# ba662.net
KiCad netlist of a schematic drawn in EAGLE
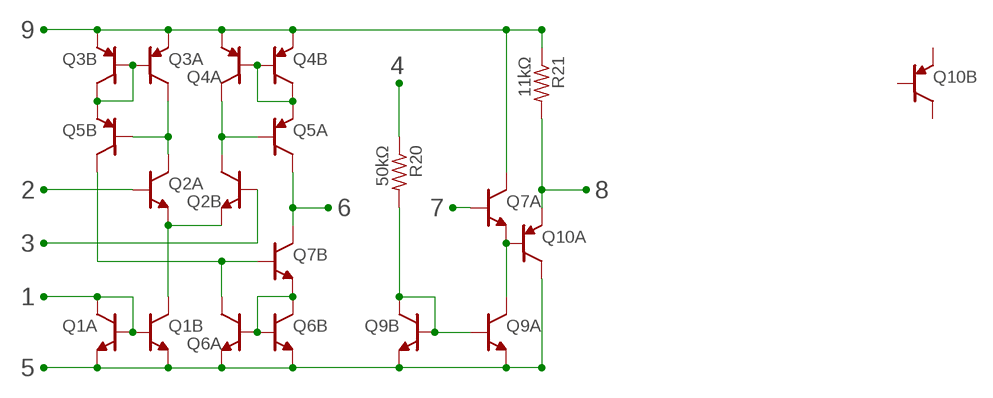
[diagram p0: schematic, sheet 1]

(export (version "E")
  (design (tool "Eeschema 10.0.6"))
  (components
    (comp (ref "Q1")
      (value "NPN-DUALPMP4201")
      (footprint "eagle-import:SOT363")
      (libsource (lib "eagle-import") (part "NPN-DUALPMP4201"))
    )
    (comp (ref "Q2")
      (value "NPN-DUALPMP4201")
      (footprint "eagle-import:SOT363")
      (libsource (lib "eagle-import") (part "NPN-DUALPMP4201"))
    )
    (comp (ref "Q3")
      (value "PNP-DUALPMP5201")
      (footprint "eagle-import:SOT363")
      (libsource (lib "eagle-import") (part "PNP-DUALPMP5201"))
    )
    (comp (ref "Q4")
      (value "PNP-DUALPMP5201")
      (footprint "eagle-import:SOT363")
      (libsource (lib "eagle-import") (part "PNP-DUALPMP5201"))
    )
    (comp (ref "Q5")
      (value "PNP-DUALPMP5201")
      (footprint "eagle-import:SOT363")
      (libsource (lib "eagle-import") (part "PNP-DUALPMP5201"))
    )
    (comp (ref "Q6")
      (value "NPN-DUALPMP4201")
      (footprint "eagle-import:SOT363")
      (libsource (lib "eagle-import") (part "NPN-DUALPMP4201"))
    )
    (comp (ref "Q7")
      (value "NPN-DUALPMP4201")
      (footprint "eagle-import:SOT363")
      (libsource (lib "eagle-import") (part "NPN-DUALPMP4201"))
    )
    (comp (ref "Q9")
      (value "NPN-DUALPMP4201")
      (footprint "eagle-import:SOT363")
      (libsource (lib "eagle-import") (part "NPN-DUALPMP4201"))
    )
    (comp (ref "Q10")
      (value "PNP-DUALPMP5201")
      (footprint "eagle-import:SOT363")
      (libsource (lib "eagle-import") (part "PNP-DUALPMP5201"))
    )
    (comp (ref "R20")
      (value "50kΩ")
      (footprint "eagle-import:0603-SM")
      (libsource (lib "eagle-import") (part "RESISTOR0603-SM"))
    )
    (comp (ref "R21")
      (value "11kΩ")
      (footprint "eagle-import:0603-SM")
      (libsource (lib "eagle-import") (part "RESISTOR0603-SM"))
    )
  )
  (nets
    (net (code "1") (name "Net-(Q1A-P$2)") (class "Default")
      (node (ref "Q1") (pin "P$1") (pinfunction "P$1_P$1") (pintype "bidirectional"))
      (node (ref "Q1") (pin "P$2") (pinfunction "P$1_P$2") (pintype "bidirectional"))
      (node (ref "Q1") (pin "P$6") (pinfunction "P$2_P$6") (pintype "bidirectional"))
    )
    (net (code "2") (name "Net-(Q1B-P$2)") (class "Default")
      (node (ref "Q1") (pin "P$3") (pinfunction "P$2_P$3") (pintype "bidirectional"))
      (node (ref "Q2") (pin "P$4") (pinfunction "P$3_P$4") (pintype "bidirectional"))
      (node (ref "Q2") (pin "P$5") (pinfunction "P$3_P$5") (pintype "bidirectional"))
    )
    (net (code "3") (name "Net-(Q2A-P$2)") (class "Default")
      (node (ref "Q2") (pin "P$6") (pinfunction "P$2_P$6") (pintype "bidirectional"))
      (node (ref "Q3") (pin "P$6") (pinfunction "P$3_P$6") (pintype "bidirectional"))
      (node (ref "Q5") (pin "P$2") (pinfunction "P$1_P$2") (pintype "bidirectional"))
    )
    (net (code "4") (name "Net-(Q2B-P$2)") (class "Default")
      (node (ref "Q2") (pin "P$3") (pinfunction "P$2_P$3") (pintype "bidirectional"))
      (node (ref "Q4") (pin "P$6") (pinfunction "P$3_P$6") (pintype "bidirectional"))
      (node (ref "Q5") (pin "P$1") (pinfunction "P$1_P$1") (pintype "bidirectional"))
    )
    (net (code "5") (name "Net-(Q3A-P$2)") (class "Default")
      (node (ref "Q3") (pin "P$4") (pinfunction "P$2_P$4") (pintype "bidirectional"))
      (node (ref "Q3") (pin "P$5") (pinfunction "P$2_P$5") (pintype "bidirectional"))
      (node (ref "Q4") (pin "P$4") (pinfunction "P$2_P$4") (pintype "bidirectional"))
      (node (ref "Q4") (pin "P$5") (pinfunction "P$2_P$5") (pintype "bidirectional"))
      (node (ref "Q7") (pin "P$6") (pinfunction "P$2_P$6") (pintype "bidirectional"))
      (node (ref "R21") (pin "P$1") (pinfunction "1_P$1") (pintype "passive"))
    )
    (net (code "6") (name "Net-(Q3B-P$1)") (class "Default")
      (node (ref "Q3") (pin "P$1") (pinfunction "P$1_P$1") (pintype "bidirectional"))
      (node (ref "Q3") (pin "P$2") (pinfunction "P$1_P$2") (pintype "bidirectional"))
      (node (ref "Q3") (pin "P$3") (pinfunction "P$3_P$3") (pintype "bidirectional"))
      (node (ref "Q5") (pin "P$4") (pinfunction "P$2_P$4") (pintype "bidirectional"))
    )
    (net (code "7") (name "Net-(Q4B-P$1)") (class "Default")
      (node (ref "Q4") (pin "P$1") (pinfunction "P$1_P$1") (pintype "bidirectional"))
      (node (ref "Q4") (pin "P$2") (pinfunction "P$1_P$2") (pintype "bidirectional"))
      (node (ref "Q4") (pin "P$3") (pinfunction "P$3_P$3") (pintype "bidirectional"))
      (node (ref "Q5") (pin "P$5") (pinfunction "P$2_P$5") (pintype "bidirectional"))
    )
    (net (code "8") (name "Net-(Q5A-P$3)") (class "Default")
      (node (ref "Q5") (pin "P$6") (pinfunction "P$3_P$6") (pintype "bidirectional"))
      (node (ref "Q7") (pin "P$3") (pinfunction "P$2_P$3") (pintype "bidirectional"))
    )
    (net (code "9") (name "Net-(Q6A-P$2)") (class "Default")
      (node (ref "Q5") (pin "P$3") (pinfunction "P$3_P$3") (pintype "bidirectional"))
      (node (ref "Q6") (pin "P$6") (pinfunction "P$2_P$6") (pintype "bidirectional"))
      (node (ref "Q7") (pin "P$2") (pinfunction "P$1_P$2") (pintype "bidirectional"))
    )
    (net (code "10") (name "Net-(Q6B-P$1)") (class "Default")
      (node (ref "Q6") (pin "P$1") (pinfunction "P$1_P$1") (pintype "bidirectional"))
      (node (ref "Q6") (pin "P$2") (pinfunction "P$1_P$2") (pintype "bidirectional"))
      (node (ref "Q6") (pin "P$3") (pinfunction "P$2_P$3") (pintype "bidirectional"))
      (node (ref "Q7") (pin "P$4") (pinfunction "P$3_P$4") (pintype "bidirectional"))
    )
    (net (code "11") (name "Net-(Q7A-P$3)") (class "Default")
      (node (ref "Q10") (pin "P$1") (pinfunction "P$1_P$1") (pintype "bidirectional"))
      (node (ref "Q7") (pin "P$5") (pinfunction "P$3_P$5") (pintype "bidirectional"))
      (node (ref "Q9") (pin "P$6") (pinfunction "P$2_P$6") (pintype "bidirectional"))
    )
    (net (code "12") (name "Net-(Q9B-P$1)") (class "Default")
      (node (ref "Q9") (pin "P$1") (pinfunction "P$1_P$1") (pintype "bidirectional"))
      (node (ref "Q9") (pin "P$2") (pinfunction "P$1_P$2") (pintype "bidirectional"))
      (node (ref "Q9") (pin "P$3") (pinfunction "P$2_P$3") (pintype "bidirectional"))
      (node (ref "R20") (pin "P$2") (pinfunction "2_P$2") (pintype "passive"))
    )
    (net (code "13") (name "Net-(Q10A-P$2)") (class "Default")
      (node (ref "Q10") (pin "P$5") (pinfunction "P$2_P$5") (pintype "bidirectional"))
      (node (ref "R21") (pin "P$2") (pinfunction "2_P$2") (pintype "passive"))
    )
    (net (code "14") (name "Net-(Q10A-P$3)") (class "Default")
      (node (ref "Q1") (pin "P$4") (pinfunction "P$3_P$4") (pintype "bidirectional"))
      (node (ref "Q1") (pin "P$5") (pinfunction "P$3_P$5") (pintype "bidirectional"))
      (node (ref "Q10") (pin "P$6") (pinfunction "P$3_P$6") (pintype "bidirectional"))
      (node (ref "Q6") (pin "P$4") (pinfunction "P$3_P$4") (pintype "bidirectional"))
      (node (ref "Q6") (pin "P$5") (pinfunction "P$3_P$5") (pintype "bidirectional"))
      (node (ref "Q9") (pin "P$4") (pinfunction "P$3_P$4") (pintype "bidirectional"))
      (node (ref "Q9") (pin "P$5") (pinfunction "P$3_P$5") (pintype "bidirectional"))
    )
    (net (code "15") (name "unconnected-(Q2-PadP$1)") (class "Default")
      (node (ref "Q2") (pin "P$1") (pinfunction "P$1_P$1") (pintype "bidirectional"))
    )
    (net (code "16") (name "unconnected-(Q2B-P$1-PadP$2)") (class "Default")
      (node (ref "Q2") (pin "P$2") (pinfunction "P$1_P$2") (pintype "bidirectional"))
    )
    (net (code "17") (name "unconnected-(Q7-PadP$1)") (class "Default")
      (node (ref "Q7") (pin "P$1") (pinfunction "P$1_P$1") (pintype "bidirectional"))
    )
    (net (code "18") (name "unconnected-(Q10-PadP$3)") (class "Default")
      (node (ref "Q10") (pin "P$3") (pinfunction "P$3_P$3") (pintype "bidirectional"))
    )
    (net (code "19") (name "unconnected-(Q10B-P$1-PadP$2)") (class "Default")
      (node (ref "Q10") (pin "P$2") (pinfunction "P$1_P$2") (pintype "bidirectional"))
    )
    (net (code "20") (name "unconnected-(Q10B-P$2-PadP$4)") (class "Default")
      (node (ref "Q10") (pin "P$4") (pinfunction "P$2_P$4") (pintype "bidirectional"))
    )
    (net (code "21") (name "unconnected-(R20-1-PadP$1)") (class "Default")
      (node (ref "R20") (pin "P$1") (pinfunction "1_P$1") (pintype "passive"))
    )
  )
)
